# FE.net
KiCad netlist of a schematic drawn in Altium Designer
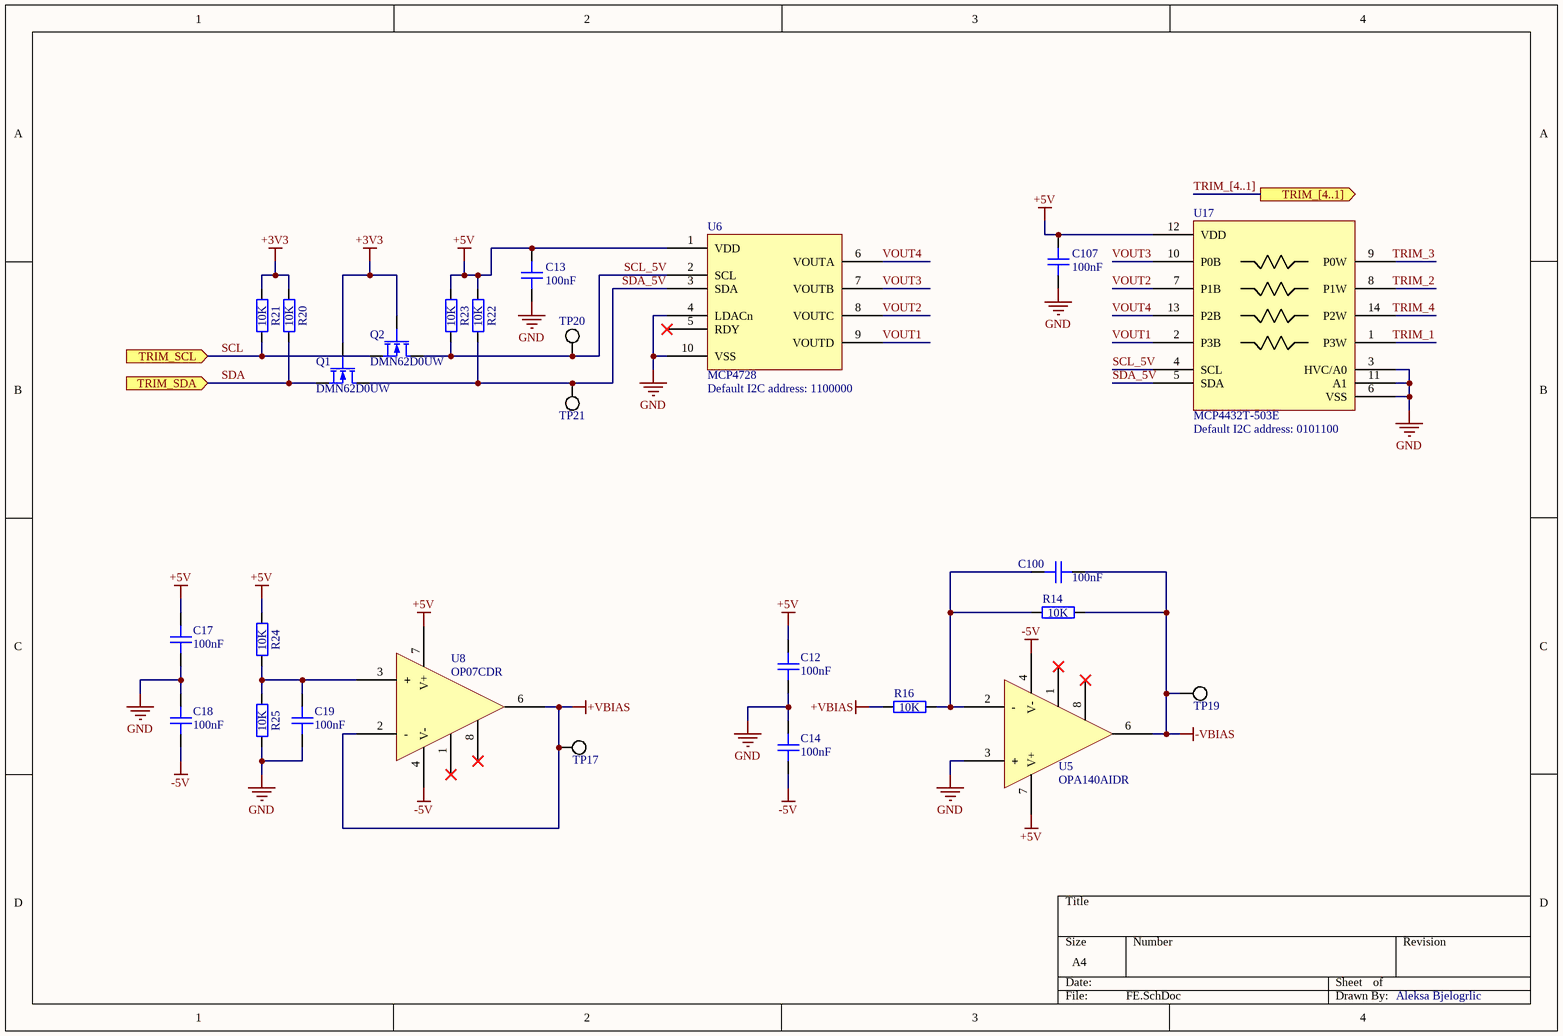
[diagram p0: FE.SchDoc]

(export (version "E")
  (design (tool "Eeschema 10.0.6"))
  (components
    (comp (ref "C12")
      (value "100nF")
      (footprint "GEN_C_0402")
      (fields
        (field (name "HOUSE PART NUMBER") "C-100nF-0402-002")
        (field (name "MANUFACTURER") "Murata")
        (field (name "MANUFACTURER PART NUMBER") "GCM155R71C104KA55D")
      )
      (libsource (lib "DSO") (part "CAP 100nF 16V X7R 0402"))
    )
    (comp (ref "C13")
      (value "100nF")
      (footprint "GEN_C_0402")
      (fields
        (field (name "HOUSE PART NUMBER") "C-100nF-0402-002")
        (field (name "MANUFACTURER") "Murata")
        (field (name "MANUFACTURER PART NUMBER") "GCM155R71C104KA55D")
      )
      (libsource (lib "DSO") (part "CAP 100nF 16V X7R 0402"))
    )
    (comp (ref "C14")
      (value "100nF")
      (footprint "GEN_C_0402")
      (fields
        (field (name "HOUSE PART NUMBER") "C-100nF-0402-002")
        (field (name "MANUFACTURER") "Murata")
        (field (name "MANUFACTURER PART NUMBER") "GCM155R71C104KA55D")
      )
      (libsource (lib "DSO") (part "CAP 100nF 16V X7R 0402"))
    )
    (comp (ref "C17")
      (value "100nF")
      (footprint "GEN_C_0402")
      (fields
        (field (name "HOUSE PART NUMBER") "C-100nF-0402-002")
        (field (name "MANUFACTURER") "Murata")
        (field (name "MANUFACTURER PART NUMBER") "GCM155R71C104KA55D")
      )
      (libsource (lib "DSO") (part "CAP 100nF 16V X7R 0402"))
    )
    (comp (ref "C18")
      (value "100nF")
      (footprint "GEN_C_0402")
      (fields
        (field (name "HOUSE PART NUMBER") "C-100nF-0402-002")
        (field (name "MANUFACTURER") "Murata")
        (field (name "MANUFACTURER PART NUMBER") "GCM155R71C104KA55D")
      )
      (libsource (lib "DSO") (part "CAP 100nF 16V X7R 0402"))
    )
    (comp (ref "C19")
      (value "100nF")
      (footprint "GEN_C_0402")
      (fields
        (field (name "HOUSE PART NUMBER") "C-100nF-0402-002")
        (field (name "MANUFACTURER") "Murata")
        (field (name "MANUFACTURER PART NUMBER") "GCM155R71C104KA55D")
      )
      (libsource (lib "DSO") (part "CAP 100nF 16V X7R 0402"))
    )
    (comp (ref "C100")
      (value "100nF")
      (footprint "GEN_C_0402")
      (fields
        (field (name "HOUSE PART NUMBER") "C-100nF-0402-002")
        (field (name "MANUFACTURER") "Murata")
        (field (name "MANUFACTURER PART NUMBER") "GCM155R71C104KA55D")
      )
      (libsource (lib "DSO") (part "CAP 100nF 16V X7R 0402"))
    )
    (comp (ref "C107")
      (value "100nF")
      (footprint "GEN_C_0402")
      (fields
        (field (name "HOUSE PART NUMBER") "C-100nF-0402-002")
        (field (name "MANUFACTURER") "Murata")
        (field (name "MANUFACTURER PART NUMBER") "GCM155R71C104KA55D")
      )
      (libsource (lib "DSO") (part "CAP 100nF 16V X7R 0402"))
    )
    (comp (ref "Q1")
      (value "DMN62D0UW")
      (footprint "GEN_SOT_323")
      (fields (field (name "HOUSE PART NUMBER") "DMN62D0UW-7") (field (name "MANUFACTURER") "Diodes"))
      (libsource (lib "DSO") (part "NMOS DMN62D0UW"))
    )
    (comp (ref "Q2")
      (value "DMN62D0UW")
      (footprint "GEN_SOT_323")
      (fields (field (name "HOUSE PART NUMBER") "DMN62D0UW-7") (field (name "MANUFACTURER") "Diodes"))
      (libsource (lib "DSO") (part "NMOS DMN62D0UW"))
    )
    (comp (ref "R14")
      (value "10K")
      (footprint "GEN_R_0402")
      (fields
        (field (name "TOLERANCE") "1%")
        (field (name "MANUFACTURER") "Panasonic")
        (field (name "MANUFACTURER PART NUMBER") "ERJ-2RKF1002X")
      )
      (libsource (lib "DSO") (part "RES 10K OHM 1% 1/10W 0402"))
    )
    (comp (ref "R16")
      (value "10K")
      (footprint "GEN_R_0402")
      (fields
        (field (name "TOLERANCE") "1%")
        (field (name "MANUFACTURER") "Panasonic")
        (field (name "MANUFACTURER PART NUMBER") "ERJ-2RKF1002X")
      )
      (libsource (lib "DSO") (part "RES 10K OHM 1% 1/10W 0402"))
    )
    (comp (ref "R20")
      (value "10K")
      (footprint "GEN_R_0402")
      (fields
        (field (name "TOLERANCE") "1%")
        (field (name "MANUFACTURER") "Panasonic")
        (field (name "MANUFACTURER PART NUMBER") "ERJ-2RKF1002X")
      )
      (libsource (lib "DSO") (part "RES 10K OHM 1% 1/10W 0402"))
    )
    (comp (ref "R21")
      (value "10K")
      (footprint "GEN_R_0402")
      (fields
        (field (name "TOLERANCE") "1%")
        (field (name "MANUFACTURER") "Panasonic")
        (field (name "MANUFACTURER PART NUMBER") "ERJ-2RKF1002X")
      )
      (libsource (lib "DSO") (part "RES 10K OHM 1% 1/10W 0402"))
    )
    (comp (ref "R22")
      (value "10K")
      (footprint "GEN_R_0402")
      (fields
        (field (name "TOLERANCE") "1%")
        (field (name "MANUFACTURER") "Panasonic")
        (field (name "MANUFACTURER PART NUMBER") "ERJ-2RKF1002X")
      )
      (libsource (lib "DSO") (part "RES 10K OHM 1% 1/10W 0402"))
    )
    (comp (ref "R23")
      (value "10K")
      (footprint "GEN_R_0402")
      (fields
        (field (name "TOLERANCE") "1%")
        (field (name "MANUFACTURER") "Panasonic")
        (field (name "MANUFACTURER PART NUMBER") "ERJ-2RKF1002X")
      )
      (libsource (lib "DSO") (part "RES 10K OHM 1% 1/10W 0402"))
    )
    (comp (ref "R24")
      (value "10K")
      (footprint "GEN_R_0402")
      (fields
        (field (name "TOLERANCE") "1%")
        (field (name "MANUFACTURER") "Panasonic")
        (field (name "MANUFACTURER PART NUMBER") "ERJ-2RKF1002X")
      )
      (libsource (lib "DSO") (part "RES 10K OHM 1% 1/10W 0402"))
    )
    (comp (ref "R25")
      (value "10K")
      (footprint "GEN_R_0402")
      (fields
        (field (name "TOLERANCE") "1%")
        (field (name "MANUFACTURER") "Panasonic")
        (field (name "MANUFACTURER PART NUMBER") "ERJ-2RKF1002X")
      )
      (libsource (lib "DSO") (part "RES 10K OHM 1% 1/10W 0402"))
    )
    (comp (ref "TP17") (value "PCB") (footprint "GEN_TP_PCB") (libsource (lib "DSO") (part "TP PCB 1mm")))
    (comp (ref "TP19") (value "PCB") (footprint "GEN_TP_PCB") (libsource (lib "DSO") (part "TP PCB 1mm")))
    (comp (ref "TP20") (value "PCB") (footprint "GEN_TP_PCB") (libsource (lib "DSO") (part "TP PCB 1mm")))
    (comp (ref "TP21") (value "PCB") (footprint "GEN_TP_PCB") (libsource (lib "DSO") (part "TP PCB 1mm")))
    (comp (ref "U5")
      (value "OPA140AIDR")
      (footprint "TI_SOIC8_D0008A")
      (fields (field (name "MANUFACTURER") "Texas Instruments"))
      (libsource (lib "DSO") (part "IC OPAMP OPA140"))
    )
    (comp (ref "U6")
      (value "MCP4728")
      (footprint "MC_MSOP10_UN")
      (fields (field (name "MANUFACTURER") "Microchip"))
      (libsource (lib "DSO") (part "IC DAC QUAD MCP4728"))
    )
    (comp (ref "U8")
      (value "OP07CDR")
      (footprint "TI_SOIC8_D0008A")
      (fields (field (name "MANUFACTURER") "Texas Instruments"))
      (libsource (lib "DSO") (part "IC OPAMP OP07CDR"))
    )
    (comp (ref "U17")
      (value "MCP4432T-503E")
      (footprint "MC_TSSOP14")
      (fields
        (field (name "MANUFACTURER") "Microchip")
        (field (name "MANUFACTURER PART NUMBER") "MCP4432T-503E/ST")
      )
      (libsource (lib "DSO") (part "IC DIGIPOT QUAD MCP4432T-503E"))
    )
  )
  (nets
    (net (code "1") (name "+3V3") (class "Default")
      (node (ref "Q1") (pin "2") (pinfunction "G_2") (pintype "passive"))
      (node (ref "Q2") (pin "2") (pinfunction "G_2") (pintype "passive"))
      (node (ref "R20") (pin "2") (pinfunction "2_2") (pintype "passive"))
      (node (ref "R21") (pin "2") (pinfunction "2_2") (pintype "passive"))
    )
    (net (code "2") (name "+5V") (class "Default")
      (node (ref "C107") (pin "2") (pinfunction "2_2") (pintype "passive"))
      (node (ref "C12") (pin "1") (pinfunction "1_1") (pintype "passive"))
      (node (ref "C13") (pin "2") (pinfunction "2_2") (pintype "passive"))
      (node (ref "C17") (pin "1") (pinfunction "1_1") (pintype "passive"))
      (node (ref "R22") (pin "2") (pinfunction "2_2") (pintype "passive"))
      (node (ref "R23") (pin "2") (pinfunction "2_2") (pintype "passive"))
      (node (ref "R24") (pin "2") (pinfunction "2_2") (pintype "passive"))
      (node (ref "U17") (pin "12") (pinfunction "VDD_12") (pintype "power_in"))
      (node (ref "U5") (pin "7") (pinfunction "V+_7") (pintype "passive"))
      (node (ref "U6") (pin "1") (pinfunction "VDD_1") (pintype "power_in"))
      (node (ref "U8") (pin "7") (pinfunction "V+_7") (pintype "passive"))
    )
    (net (code "3") (name "+VBIAS") (class "Default")
      (node (ref "R16") (pin "1") (pinfunction "1_1") (pintype "passive"))
      (node (ref "TP17") (pin "1") (pinfunction "1_1") (pintype "passive"))
      (node (ref "U8") (pin "2") (pinfunction "-_2") (pintype "passive"))
      (node (ref "U8") (pin "6") (pinfunction "OUT_6") (pintype "passive"))
    )
    (net (code "4") (name "-5V") (class "Default")
      (node (ref "C14") (pin "2") (pinfunction "2_2") (pintype "passive"))
      (node (ref "C18") (pin "2") (pinfunction "2_2") (pintype "passive"))
      (node (ref "U5") (pin "4") (pinfunction "V-_4") (pintype "passive"))
      (node (ref "U8") (pin "4") (pinfunction "V-_4") (pintype "passive"))
    )
    (net (code "5") (name "-VBIAS") (class "Default")
      (node (ref "C100") (pin "1") (pinfunction "1_1") (pintype "passive"))
      (node (ref "R14") (pin "2") (pinfunction "2_2") (pintype "passive"))
      (node (ref "TP19") (pin "1") (pinfunction "1_1") (pintype "passive"))
      (node (ref "U5") (pin "6") (pinfunction "OUT_6") (pintype "passive"))
    )
    (net (code "6") (name "/SCL") (class "Default")
      (node (ref "Q2") (pin "3") (pinfunction "S_3") (pintype "passive"))
      (node (ref "R21") (pin "1") (pinfunction "1_1") (pintype "passive"))
    )
    (net (code "7") (name "/SCL_5V") (class "Default")
      (node (ref "Q2") (pin "1") (pinfunction "D_1") (pintype "passive"))
      (node (ref "R23") (pin "1") (pinfunction "1_1") (pintype "passive"))
      (node (ref "TP20") (pin "1") (pinfunction "1_1") (pintype "passive"))
      (node (ref "U17") (pin "4") (pinfunction "SCL_4") (pintype "passive"))
      (node (ref "U6") (pin "2") (pinfunction "SCL_2") (pintype "passive"))
    )
    (net (code "8") (name "/SDA") (class "Default")
      (node (ref "Q1") (pin "3") (pinfunction "S_3") (pintype "passive"))
      (node (ref "R20") (pin "1") (pinfunction "1_1") (pintype "passive"))
    )
    (net (code "9") (name "/SDA_5V") (class "Default")
      (node (ref "Q1") (pin "1") (pinfunction "D_1") (pintype "passive"))
      (node (ref "R22") (pin "1") (pinfunction "1_1") (pintype "passive"))
      (node (ref "TP21") (pin "1") (pinfunction "1_1") (pintype "passive"))
      (node (ref "U17") (pin "5") (pinfunction "SDA_5") (pintype "passive"))
      (node (ref "U6") (pin "3") (pinfunction "SDA_3") (pintype "passive"))
    )
    (net (code "10") (name "/TRIM_1") (class "Default")
      (node (ref "U17") (pin "1") (pinfunction "P3W_1") (pintype "passive"))
    )
    (net (code "11") (name "/TRIM_2") (class "Default")
      (node (ref "U17") (pin "8") (pinfunction "P1W_8") (pintype "passive"))
    )
    (net (code "12") (name "/TRIM_3") (class "Default")
      (node (ref "U17") (pin "9") (pinfunction "P0W_9") (pintype "passive"))
    )
    (net (code "13") (name "/TRIM_4") (class "Default")
      (node (ref "U17") (pin "14") (pinfunction "P2W_14") (pintype "passive"))
    )
    (net (code "15") (name "/VOUT1") (class "Default")
      (node (ref "U17") (pin "2") (pinfunction "P3B_2") (pintype "passive"))
      (node (ref "U6") (pin "9") (pinfunction "VOUTD_9") (pintype "passive"))
    )
    (net (code "16") (name "/VOUT2") (class "Default")
      (node (ref "U17") (pin "7") (pinfunction "P1B_7") (pintype "passive"))
      (node (ref "U6") (pin "8") (pinfunction "VOUTC_8") (pintype "passive"))
    )
    (net (code "17") (name "/VOUT3") (class "Default")
      (node (ref "U17") (pin "10") (pinfunction "P0B_10") (pintype "passive"))
      (node (ref "U6") (pin "7") (pinfunction "VOUTB_7") (pintype "passive"))
    )
    (net (code "18") (name "/VOUT4") (class "Default")
      (node (ref "U17") (pin "13") (pinfunction "P2B_13") (pintype "passive"))
      (node (ref "U6") (pin "6") (pinfunction "VOUTA_6") (pintype "passive"))
    )
    (net (code "19") (name "GND") (class "Default")
      (node (ref "C107") (pin "1") (pinfunction "1_1") (pintype "passive"))
      (node (ref "C12") (pin "2") (pinfunction "2_2") (pintype "passive"))
      (node (ref "C13") (pin "1") (pinfunction "1_1") (pintype "passive"))
      (node (ref "C14") (pin "1") (pinfunction "1_1") (pintype "passive"))
      (node (ref "C17") (pin "2") (pinfunction "2_2") (pintype "passive"))
      (node (ref "C18") (pin "1") (pinfunction "1_1") (pintype "passive"))
      (node (ref "C19") (pin "1") (pinfunction "1_1") (pintype "passive"))
      (node (ref "R25") (pin "1") (pinfunction "1_1") (pintype "passive"))
      (node (ref "U17") (pin "11") (pinfunction "A1_11") (pintype "passive"))
      (node (ref "U17") (pin "3") (pinfunction "HVC/A0_3") (pintype "passive"))
      (node (ref "U17") (pin "6") (pinfunction "VSS_6") (pintype "power_in"))
      (node (ref "U5") (pin "3") (pinfunction "+_3") (pintype "passive"))
      (node (ref "U6") (pin "10") (pinfunction "VSS_10") (pintype "power_in"))
      (node (ref "U6") (pin "4") (pinfunction "LDACn_4") (pintype "passive"))
    )
    (net (code "20") (name "Net-(U5--)") (class "Default")
      (node (ref "C100") (pin "2") (pinfunction "2_2") (pintype "passive"))
      (node (ref "R14") (pin "1") (pinfunction "1_1") (pintype "passive"))
      (node (ref "R16") (pin "2") (pinfunction "2_2") (pintype "passive"))
      (node (ref "U5") (pin "2") (pinfunction "-_2") (pintype "passive"))
    )
    (net (code "21") (name "Net-(U8-+)") (class "Default")
      (node (ref "C19") (pin "2") (pinfunction "2_2") (pintype "passive"))
      (node (ref "R24") (pin "1") (pinfunction "1_1") (pintype "passive"))
      (node (ref "R25") (pin "2") (pinfunction "2_2") (pintype "passive"))
      (node (ref "U8") (pin "3") (pinfunction "+_3") (pintype "passive"))
    )
    (net (code "22") (name "unconnected-(U5-N1-Pad1)") (class "Default")
      (node (ref "U5") (pin "1") (pinfunction "N1_1") (pintype "passive+no_connect"))
    )
    (net (code "23") (name "unconnected-(U5-N2-Pad8)") (class "Default")
      (node (ref "U5") (pin "8") (pinfunction "N2_8") (pintype "passive+no_connect"))
    )
    (net (code "24") (name "unconnected-(U6-RDY-Pad5)") (class "Default")
      (node (ref "U6") (pin "5") (pinfunction "RDY_5") (pintype "passive+no_connect"))
    )
    (net (code "25") (name "unconnected-(U8-N1-Pad1)") (class "Default")
      (node (ref "U8") (pin "1") (pinfunction "N1_1") (pintype "passive+no_connect"))
    )
    (net (code "26") (name "unconnected-(U8-N2-Pad8)") (class "Default")
      (node (ref "U8") (pin "8") (pinfunction "N2_8") (pintype "passive+no_connect"))
    )
  )
)
